# Mega8.net
KiCad netlist of a schematic drawn in EAGLE
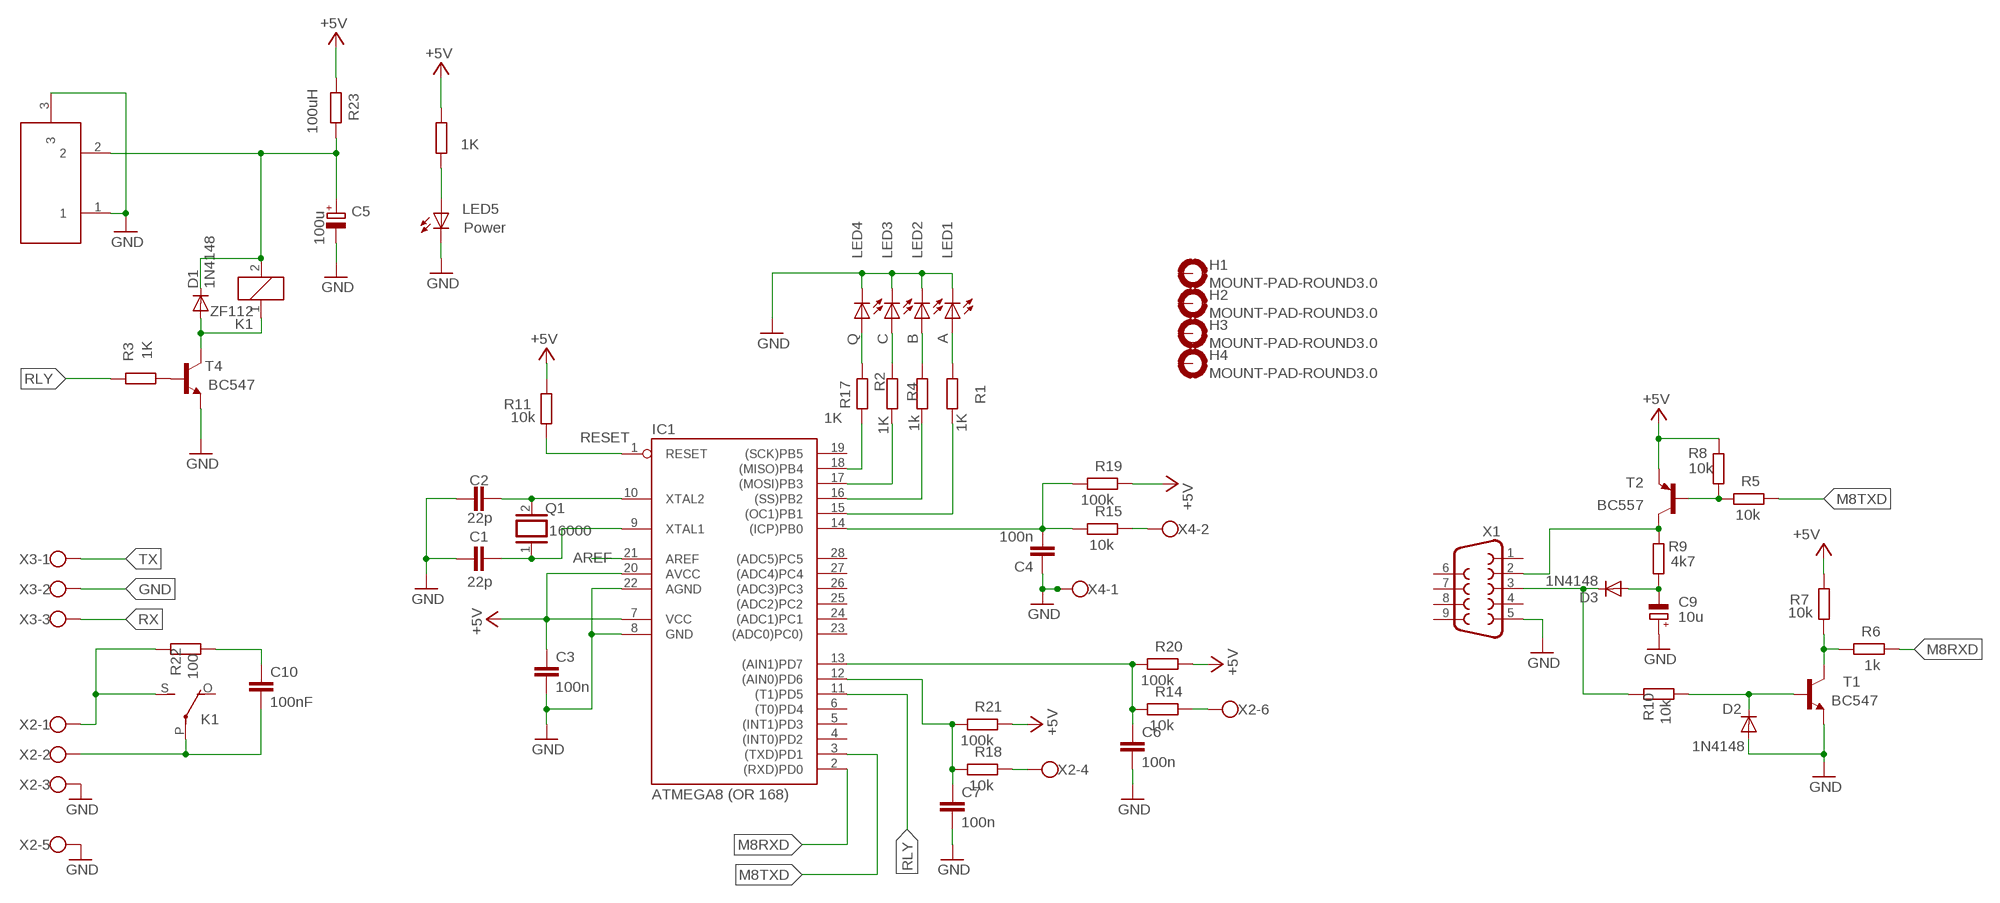
[diagram p0: schematic, sheet 1]

(export (version "E")
  (design (tool "Eeschema 10.0.6"))
  (components
    (comp (ref "C1")
      (value "22p")
      (footprint "eagle-import:C050-025X075")
      (libsource (lib "eagle-import") (part "C-EU050-025X075"))
    )
    (comp (ref "C2")
      (value "22p")
      (footprint "eagle-import:C050-025X075")
      (libsource (lib "eagle-import") (part "C-EU050-025X075"))
    )
    (comp (ref "C3")
      (value "100n")
      (footprint "eagle-import:C050-025X075")
      (libsource (lib "eagle-import") (part "C-EU050-025X075"))
    )
    (comp (ref "C4")
      (value "100n")
      (footprint "eagle-import:C050-025X075")
      (libsource (lib "eagle-import") (part "C-EU050-025X075"))
    )
    (comp (ref "C5")
      (value "100u")
      (footprint "eagle-import:E3,5-8")
      (libsource (lib "eagle-import") (part "CPOL-EUE3.5-8"))
    )
    (comp (ref "C6")
      (value "100n")
      (footprint "eagle-import:C050-025X075")
      (libsource (lib "eagle-import") (part "C-EU050-025X075"))
    )
    (comp (ref "C7")
      (value "100n")
      (footprint "eagle-import:C050-025X075")
      (libsource (lib "eagle-import") (part "C-EU050-025X075"))
    )
    (comp (ref "C9")
      (value "10u")
      (footprint "eagle-import:E5-6")
      (libsource (lib "eagle-import") (part "CPOL-EUE5-6"))
    )
    (comp (ref "C10")
      (value "100nF")
      (footprint "eagle-import:C102-043X133")
      (libsource (lib "eagle-import") (part "C-EU102-043X133"))
    )
    (comp (ref "D1")
      (value "1N4148")
      (footprint "eagle-import:DO35-10")
      (libsource (lib "eagle-import") (part "1N4148"))
    )
    (comp (ref "D2")
      (value "1N4148")
      (footprint "eagle-import:DO35-10")
      (libsource (lib "eagle-import") (part "1N4148"))
    )
    (comp (ref "D3")
      (value "1N4148")
      (footprint "eagle-import:DO35-10")
      (libsource (lib "eagle-import") (part "1N4148"))
    )
    (comp (ref "DC1")
      (value "DC21MMX")
      (footprint "eagle-import:DC-21MM")
      (libsource (lib "eagle-import") (part "DC21MMX"))
    )
    (comp (ref "H1")
      (value "MOUNT-PAD-ROUND3.0")
      (footprint "eagle-import:3,0-PAD")
      (libsource (lib "eagle-import") (part "MOUNT-PAD-ROUND3.0"))
    )
    (comp (ref "H2")
      (value "MOUNT-PAD-ROUND3.0")
      (footprint "eagle-import:3,0-PAD")
      (libsource (lib "eagle-import") (part "MOUNT-PAD-ROUND3.0"))
    )
    (comp (ref "H3")
      (value "MOUNT-PAD-ROUND3.0")
      (footprint "eagle-import:3,0-PAD")
      (libsource (lib "eagle-import") (part "MOUNT-PAD-ROUND3.0"))
    )
    (comp (ref "H4")
      (value "MOUNT-PAD-ROUND3.0")
      (footprint "eagle-import:3,0-PAD")
      (libsource (lib "eagle-import") (part "MOUNT-PAD-ROUND3.0"))
    )
    (comp (ref "IC1")
      (value "ATMEGA8 (OR 168)")
      (footprint "eagle-import:DIL28-3")
      (libsource (lib "eagle-import") (part "AT90S4433P"))
    )
    (comp (ref "K1")
      (value "ZF112")
      (footprint "eagle-import:ZF112")
      (libsource (lib "eagle-import") (part "ZF112"))
    )
    (comp (ref "LED1")
      (value "A")
      (footprint "eagle-import:LED3MM")
      (libsource (lib "eagle-import") (part "LED3MM"))
    )
    (comp (ref "LED2")
      (value "B")
      (footprint "eagle-import:LED3MM")
      (libsource (lib "eagle-import") (part "LED3MM"))
    )
    (comp (ref "LED3")
      (value "C")
      (footprint "eagle-import:LED3MM")
      (libsource (lib "eagle-import") (part "LED3MM"))
    )
    (comp (ref "LED4")
      (value "Q")
      (footprint "eagle-import:LED3MM")
      (libsource (lib "eagle-import") (part "LED3MM"))
    )
    (comp (ref "LED5")
      (value "Power")
      (footprint "eagle-import:LED3MM")
      (libsource (lib "eagle-import") (part "LED3MM"))
    )
    (comp (ref "Q1")
      (value "16000")
      (footprint "eagle-import:Q")
      (libsource (lib "eagle-import") (part "XTAL"))
    )
    (comp (ref "R1")
      (value "1K")
      (footprint "eagle-import:0207_10")
      (libsource (lib "eagle-import") (part "R-EU_0207/10"))
    )
    (comp (ref "R2")
      (value "1K")
      (footprint "eagle-import:0207_10")
      (libsource (lib "eagle-import") (part "R-EU_0207/10"))
    )
    (comp (ref "R3")
      (value "1K")
      (footprint "eagle-import:0207_10")
      (libsource (lib "eagle-import") (part "R-EU_0207/10"))
    )
    (comp (ref "R4")
      (value "1k")
      (footprint "eagle-import:0207_10")
      (libsource (lib "eagle-import") (part "R-EU_0207/10"))
    )
    (comp (ref "R5")
      (value "10k")
      (footprint "eagle-import:0207_10")
      (libsource (lib "eagle-import") (part "R-EU_0207/10"))
    )
    (comp (ref "R6")
      (value "1k")
      (footprint "eagle-import:0207_10")
      (libsource (lib "eagle-import") (part "R-EU_0207/10"))
    )
    (comp (ref "R7")
      (value "10k")
      (footprint "eagle-import:0207_10")
      (libsource (lib "eagle-import") (part "R-EU_0207/10"))
    )
    (comp (ref "R8")
      (value "10k")
      (footprint "eagle-import:0207_10")
      (libsource (lib "eagle-import") (part "R-EU_0207/10"))
    )
    (comp (ref "R9")
      (value "4k7")
      (footprint "eagle-import:0207_10")
      (libsource (lib "eagle-import") (part "R-EU_0207/10"))
    )
    (comp (ref "R10")
      (value "10k")
      (footprint "eagle-import:0207_10")
      (libsource (lib "eagle-import") (part "R-EU_0207/10"))
    )
    (comp (ref "R11")
      (value "10k")
      (footprint "eagle-import:0207_10")
      (libsource (lib "eagle-import") (part "R-EU_0207/10"))
    )
    (comp (ref "R14")
      (value "10k")
      (footprint "eagle-import:0207_10")
      (libsource (lib "eagle-import") (part "R-EU_0207/10"))
    )
    (comp (ref "R15")
      (value "10k")
      (footprint "eagle-import:0207_10")
      (libsource (lib "eagle-import") (part "R-EU_0207/10"))
    )
    (comp (ref "R16")
      (value "1K")
      (footprint "eagle-import:0207_10")
      (libsource (lib "eagle-import") (part "R-EU_0207/10"))
    )
    (comp (ref "R17")
      (value "1K")
      (footprint "eagle-import:0207_10")
      (libsource (lib "eagle-import") (part "R-EU_0207/10"))
    )
    (comp (ref "R18")
      (value "10k")
      (footprint "eagle-import:0207_10")
      (libsource (lib "eagle-import") (part "R-EU_0207/10"))
    )
    (comp (ref "R19")
      (value "100k")
      (footprint "eagle-import:0207_10")
      (libsource (lib "eagle-import") (part "R-EU_0207/10"))
    )
    (comp (ref "R20")
      (value "100k")
      (footprint "eagle-import:0207_10")
      (libsource (lib "eagle-import") (part "R-EU_0207/10"))
    )
    (comp (ref "R21")
      (value "100k")
      (footprint "eagle-import:0207_10")
      (libsource (lib "eagle-import") (part "R-EU_0207/10"))
    )
    (comp (ref "R22")
      (value "100")
      (footprint "eagle-import:0207_10")
      (libsource (lib "eagle-import") (part "R-EU_0207/10"))
    )
    (comp (ref "R23")
      (value "100uH")
      (footprint "eagle-import:0207_10")
      (libsource (lib "eagle-import") (part "R-EU_0207/10"))
    )
    (comp (ref "T1")
      (value "BC547")
      (footprint "eagle-import:TO92")
      (libsource (lib "eagle-import") (part "BC547"))
    )
    (comp (ref "T2")
      (value "BC557")
      (footprint "eagle-import:TO92-EBC")
      (libsource (lib "eagle-import") (part "-PNP-TO92-EBCBC557B"))
    )
    (comp (ref "T4")
      (value "BC547")
      (footprint "eagle-import:TO92")
      (libsource (lib "eagle-import") (part "BC547"))
    )
    (comp (ref "X1")
      (value "F09H")
      (footprint "eagle-import:F09H")
      (libsource (lib "eagle-import") (part "F09H"))
    )
    (comp (ref "X2")
      (value "W237-6")
      (footprint "eagle-import:W237-6")
      (libsource (lib "eagle-import") (part "W237-6"))
    )
    (comp (ref "X3")
      (value "W237-103")
      (footprint "eagle-import:W237-103")
      (fields (field (name "MPN") "237-103"))
      (libsource (lib "eagle-import") (part "W237-103"))
    )
    (comp (ref "X4")
      (value "W237-102")
      (footprint "eagle-import:W237-102")
      (fields (field (name "MPN") "237-102"))
      (libsource (lib "eagle-import") (part "W237-102"))
    )
  )
  (nets
    (net (code "1") (name "+5V") (class "Default")
      (node (ref "C3") (pin "1") (pinfunction "1_1") (pintype "passive"))
      (node (ref "IC1") (pin "20") (pinfunction "AVCC_20") (pintype "power_in"))
      (node (ref "IC1") (pin "7") (pinfunction "VCC_7") (pintype "power_in"))
      (node (ref "R11") (pin "2") (pinfunction "2_2") (pintype "passive"))
      (node (ref "R16") (pin "2") (pinfunction "2_2") (pintype "passive"))
      (node (ref "R19") (pin "1") (pinfunction "1_1") (pintype "passive"))
      (node (ref "R20") (pin "1") (pinfunction "1_1") (pintype "passive"))
      (node (ref "R21") (pin "1") (pinfunction "1_1") (pintype "passive"))
      (node (ref "R23") (pin "2") (pinfunction "2_2") (pintype "passive"))
      (node (ref "R7") (pin "2") (pinfunction "2_2") (pintype "passive"))
      (node (ref "R8") (pin "1") (pinfunction "1_1") (pintype "passive"))
      (node (ref "T2") (pin "E") (pinfunction "E_E") (pintype "passive"))
    )
    (net (code "2") (name "/AREF") (class "Default")
      (node (ref "IC1") (pin "21") (pinfunction "AREF_21") (pintype "power_in"))
    )
    (net (code "3") (name "/RESET") (class "Default")
      (node (ref "IC1") (pin "1") (pinfunction "RESET_1") (pintype "input"))
      (node (ref "R11") (pin "1") (pinfunction "1_1") (pintype "passive"))
    )
    (net (code "4") (name "GND") (class "Default")
      (node (ref "C1") (pin "1") (pinfunction "1_1") (pintype "passive"))
      (node (ref "C2") (pin "1") (pinfunction "1_1") (pintype "passive"))
      (node (ref "C3") (pin "2") (pinfunction "2_2") (pintype "passive"))
      (node (ref "C4") (pin "1") (pinfunction "1_1") (pintype "passive"))
      (node (ref "C5") (pin "-") (pinfunction "-_-") (pintype "passive"))
      (node (ref "C6") (pin "2") (pinfunction "2_2") (pintype "passive"))
      (node (ref "C7") (pin "2") (pinfunction "2_2") (pintype "passive"))
      (node (ref "C9") (pin "+") (pinfunction "+_+") (pintype "passive"))
      (node (ref "D2") (pin "A") (pinfunction "A_A") (pintype "passive"))
      (node (ref "DC1") (pin "1") (pinfunction "1_1") (pintype "power_in"))
      (node (ref "DC1") (pin "3") (pinfunction "3_3") (pintype "power_in"))
      (node (ref "IC1") (pin "22") (pinfunction "AGND_22") (pintype "power_in"))
      (node (ref "IC1") (pin "8") (pinfunction "GND_8") (pintype "power_in"))
      (node (ref "LED1") (pin "K") (pinfunction "C_K") (pintype "passive"))
      (node (ref "LED2") (pin "K") (pinfunction "C_K") (pintype "passive"))
      (node (ref "LED3") (pin "K") (pinfunction "C_K") (pintype "passive"))
      (node (ref "LED4") (pin "K") (pinfunction "C_K") (pintype "passive"))
      (node (ref "LED5") (pin "K") (pinfunction "C_K") (pintype "passive"))
      (node (ref "T1") (pin "1") (pinfunction "E_1") (pintype "passive"))
      (node (ref "T4") (pin "1") (pinfunction "E_1") (pintype "passive"))
      (node (ref "X1") (pin "5") (pinfunction "5_5") (pintype "passive"))
      (node (ref "X2") (pin "3") (pinfunction "KL_3") (pintype "passive"))
      (node (ref "X2") (pin "5") (pinfunction "KL_5") (pintype "passive"))
      (node (ref "X3") (pin "2") (pinfunction "KL_2") (pintype "passive"))
      (node (ref "X4") (pin "1") (pinfunction "KL_1") (pintype "passive"))
    )
    (net (code "5") (name "M8RXD") (class "Default")
      (node (ref "IC1") (pin "2") (pinfunction "(RXD)PD0_2") (pintype "bidirectional"))
      (node (ref "R6") (pin "1") (pinfunction "1_1") (pintype "passive"))
    )
    (net (code "6") (name "M8TXD") (class "Default")
      (node (ref "IC1") (pin "3") (pinfunction "(TXD)PD1_3") (pintype "bidirectional"))
      (node (ref "R5") (pin "1") (pinfunction "1_1") (pintype "passive"))
    )
    (net (code "7") (name "Net-(C5-Pad+)") (class "Default")
      (node (ref "C5") (pin "+") (pinfunction "+_+") (pintype "passive"))
      (node (ref "D1") (pin "C") (pinfunction "C_C") (pintype "passive"))
      (node (ref "DC1") (pin "2") (pinfunction "2_2") (pintype "power_in"))
      (node (ref "K1") (pin "2") (pinfunction "2_2") (pintype "passive"))
      (node (ref "R23") (pin "1") (pinfunction "1_1") (pintype "passive"))
    )
    (net (code "8") (name "Net-(C9-Pad-)") (class "Default")
      (node (ref "C9") (pin "-") (pinfunction "-_-") (pintype "passive"))
      (node (ref "D3") (pin "A") (pinfunction "A_A") (pintype "passive"))
      (node (ref "R9") (pin "1") (pinfunction "1_1") (pintype "passive"))
    )
    (net (code "9") (name "Net-(C10-Pad1)") (class "Default")
      (node (ref "C10") (pin "1") (pinfunction "1_1") (pintype "passive"))
      (node (ref "R22") (pin "1") (pinfunction "1_1") (pintype "passive"))
    )
    (net (code "10") (name "Net-(IC1-(AIN0)PD6)") (class "Default")
      (node (ref "C7") (pin "1") (pinfunction "1_1") (pintype "passive"))
      (node (ref "IC1") (pin "12") (pinfunction "(AIN0)PD6_12") (pintype "bidirectional"))
      (node (ref "R18") (pin "2") (pinfunction "2_2") (pintype "passive"))
      (node (ref "R21") (pin "2") (pinfunction "2_2") (pintype "passive"))
    )
    (net (code "11") (name "Net-(IC1-(AIN1)PD7)") (class "Default")
      (node (ref "C6") (pin "1") (pinfunction "1_1") (pintype "passive"))
      (node (ref "IC1") (pin "13") (pinfunction "(AIN1)PD7_13") (pintype "bidirectional"))
      (node (ref "R14") (pin "2") (pinfunction "2_2") (pintype "passive"))
      (node (ref "R20") (pin "2") (pinfunction "2_2") (pintype "passive"))
    )
    (net (code "12") (name "Net-(IC1-(ICP)PB0)") (class "Default")
      (node (ref "C4") (pin "2") (pinfunction "2_2") (pintype "passive"))
      (node (ref "IC1") (pin "14") (pinfunction "(ICP)PB0_14") (pintype "bidirectional"))
      (node (ref "R15") (pin "2") (pinfunction "2_2") (pintype "passive"))
      (node (ref "R19") (pin "2") (pinfunction "2_2") (pintype "passive"))
    )
    (net (code "13") (name "Net-(IC1-(MISO)PB4)") (class "Default")
      (node (ref "IC1") (pin "18") (pinfunction "(MISO)PB4_18") (pintype "bidirectional"))
      (node (ref "R17") (pin "2") (pinfunction "2_2") (pintype "passive"))
    )
    (net (code "14") (name "Net-(IC1-(MOSI)PB3)") (class "Default")
      (node (ref "IC1") (pin "17") (pinfunction "(MOSI)PB3_17") (pintype "bidirectional"))
      (node (ref "R2") (pin "2") (pinfunction "2_2") (pintype "passive"))
    )
    (net (code "15") (name "Net-(IC1-(OC1)PB1)") (class "Default")
      (node (ref "IC1") (pin "15") (pinfunction "(OC1)PB1_15") (pintype "bidirectional"))
      (node (ref "R1") (pin "2") (pinfunction "2_2") (pintype "passive"))
    )
    (net (code "16") (name "Net-(IC1-(SS)PB2)") (class "Default")
      (node (ref "IC1") (pin "16") (pinfunction "(SS)PB2_16") (pintype "bidirectional"))
      (node (ref "R4") (pin "2") (pinfunction "2_2") (pintype "passive"))
    )
    (net (code "17") (name "Net-(IC1-XTAL1)") (class "Default")
      (node (ref "C1") (pin "2") (pinfunction "2_2") (pintype "passive"))
      (node (ref "IC1") (pin "9") (pinfunction "XTAL1_9") (pintype "bidirectional"))
      (node (ref "Q1") (pin "1") (pinfunction "1_1") (pintype "passive"))
    )
    (net (code "18") (name "Net-(IC1-XTAL2)") (class "Default")
      (node (ref "C2") (pin "2") (pinfunction "2_2") (pintype "passive"))
      (node (ref "IC1") (pin "10") (pinfunction "XTAL2_10") (pintype "bidirectional"))
      (node (ref "Q1") (pin "2") (pinfunction "2_2") (pintype "passive"))
    )
    (net (code "19") (name "Net-(LED1-PadA)") (class "Default")
      (node (ref "LED1") (pin "A") (pinfunction "A_A") (pintype "passive"))
      (node (ref "R1") (pin "1") (pinfunction "1_1") (pintype "passive"))
    )
    (net (code "20") (name "Net-(LED2-PadA)") (class "Default")
      (node (ref "LED2") (pin "A") (pinfunction "A_A") (pintype "passive"))
      (node (ref "R4") (pin "1") (pinfunction "1_1") (pintype "passive"))
    )
    (net (code "21") (name "Net-(LED3-PadA)") (class "Default")
      (node (ref "LED3") (pin "A") (pinfunction "A_A") (pintype "passive"))
      (node (ref "R2") (pin "1") (pinfunction "1_1") (pintype "passive"))
    )
    (net (code "22") (name "Net-(LED4-PadA)") (class "Default")
      (node (ref "LED4") (pin "A") (pinfunction "A_A") (pintype "passive"))
      (node (ref "R17") (pin "1") (pinfunction "1_1") (pintype "passive"))
    )
    (net (code "23") (name "Net-(LED5-PadA)") (class "Default")
      (node (ref "LED5") (pin "A") (pinfunction "A_A") (pintype "passive"))
      (node (ref "R16") (pin "1") (pinfunction "1_1") (pintype "passive"))
    )
    (net (code "24") (name "Net-(R5-Pad2)") (class "Default")
      (node (ref "R5") (pin "2") (pinfunction "2_2") (pintype "passive"))
      (node (ref "R8") (pin "2") (pinfunction "2_2") (pintype "passive"))
      (node (ref "T2") (pin "B") (pinfunction "B_B") (pintype "passive"))
    )
    (net (code "25") (name "Net-(T1-B)") (class "Default")
      (node (ref "D2") (pin "C") (pinfunction "C_C") (pintype "passive"))
      (node (ref "R10") (pin "1") (pinfunction "1_1") (pintype "passive"))
      (node (ref "T1") (pin "2") (pinfunction "B_2") (pintype "passive"))
    )
    (net (code "26") (name "Net-(T1-C)") (class "Default")
      (node (ref "R6") (pin "2") (pinfunction "2_2") (pintype "passive"))
      (node (ref "R7") (pin "1") (pinfunction "1_1") (pintype "passive"))
      (node (ref "T1") (pin "3") (pinfunction "C_3") (pintype "passive"))
    )
    (net (code "27") (name "Net-(T4-B)") (class "Default")
      (node (ref "R3") (pin "1") (pinfunction "1_1") (pintype "passive"))
      (node (ref "T4") (pin "2") (pinfunction "B_2") (pintype "passive"))
    )
    (net (code "28") (name "Net-(T4-C)") (class "Default")
      (node (ref "D1") (pin "A") (pinfunction "A_A") (pintype "passive"))
      (node (ref "K1") (pin "1") (pinfunction "1_1") (pintype "passive"))
      (node (ref "T4") (pin "3") (pinfunction "C_3") (pintype "passive"))
    )
    (net (code "29") (name "Net-(X2A-KL)") (class "Default")
      (node (ref "K1") (pin "S") (pinfunction "S_S") (pintype "passive"))
      (node (ref "R22") (pin "2") (pinfunction "2_2") (pintype "passive"))
      (node (ref "X2") (pin "1") (pinfunction "KL_1") (pintype "passive"))
    )
    (net (code "30") (name "Net-(X2B-KL)") (class "Default")
      (node (ref "C10") (pin "2") (pinfunction "2_2") (pintype "passive"))
      (node (ref "K1") (pin "P") (pinfunction "P_P") (pintype "passive"))
      (node (ref "X2") (pin "2") (pinfunction "KL_2") (pintype "passive"))
    )
    (net (code "31") (name "Net-(X2D-KL)") (class "Default")
      (node (ref "R18") (pin "1") (pinfunction "1_1") (pintype "passive"))
      (node (ref "X2") (pin "4") (pinfunction "KL_4") (pintype "passive"))
    )
    (net (code "32") (name "Net-(X2F-KL)") (class "Default")
      (node (ref "R14") (pin "1") (pinfunction "1_1") (pintype "passive"))
      (node (ref "X2") (pin "6") (pinfunction "KL_6") (pintype "passive"))
    )
    (net (code "33") (name "Net-(X4B-KL)") (class "Default")
      (node (ref "R15") (pin "1") (pinfunction "1_1") (pintype "passive"))
      (node (ref "X4") (pin "2") (pinfunction "KL_2") (pintype "passive"))
    )
    (net (code "34") (name "RLY") (class "Default")
      (node (ref "IC1") (pin "11") (pinfunction "(T1)PD5_11") (pintype "bidirectional"))
      (node (ref "R3") (pin "2") (pinfunction "2_2") (pintype "passive"))
    )
    (net (code "35") (name "RX") (class "Default")
      (node (ref "D3") (pin "C") (pinfunction "C_C") (pintype "passive"))
      (node (ref "R10") (pin "2") (pinfunction "2_2") (pintype "passive"))
      (node (ref "X1") (pin "3") (pinfunction "3_3") (pintype "passive"))
      (node (ref "X3") (pin "3") (pinfunction "KL_3") (pintype "passive"))
    )
    (net (code "36") (name "TX") (class "Default")
      (node (ref "R9") (pin "2") (pinfunction "2_2") (pintype "passive"))
      (node (ref "T2") (pin "C") (pinfunction "C_C") (pintype "passive"))
      (node (ref "X1") (pin "2") (pinfunction "2_2") (pintype "passive"))
      (node (ref "X3") (pin "1") (pinfunction "KL_1") (pintype "passive"))
    )
    (net (code "37") (name "unconnected-(H1-MOUNT-PadB3,0)") (class "Default")
      (node (ref "H1") (pin "B3,0") (pinfunction "MOUNT_B3,0") (pintype "passive"))
    )
    (net (code "38") (name "unconnected-(H2-MOUNT-PadB3,0)") (class "Default")
      (node (ref "H2") (pin "B3,0") (pinfunction "MOUNT_B3,0") (pintype "passive"))
    )
    (net (code "39") (name "unconnected-(H3-MOUNT-PadB3,0)") (class "Default")
      (node (ref "H3") (pin "B3,0") (pinfunction "MOUNT_B3,0") (pintype "passive"))
    )
    (net (code "40") (name "unconnected-(H4-MOUNT-PadB3,0)") (class "Default")
      (node (ref "H4") (pin "B3,0") (pinfunction "MOUNT_B3,0") (pintype "passive"))
    )
    (net (code "41") (name "unconnected-(IC1-(ADC0)PC0)-Pad23)") (class "Default")
      (node (ref "IC1") (pin "23") (pinfunction "(ADC0)PC0)_23") (pintype "bidirectional"))
    )
    (net (code "42") (name "unconnected-(IC1-(ADC1)PC1-Pad24)") (class "Default")
      (node (ref "IC1") (pin "24") (pinfunction "(ADC1)PC1_24") (pintype "bidirectional"))
    )
    (net (code "43") (name "unconnected-(IC1-(ADC2)PC2-Pad25)") (class "Default")
      (node (ref "IC1") (pin "25") (pinfunction "(ADC2)PC2_25") (pintype "bidirectional"))
    )
    (net (code "44") (name "unconnected-(IC1-(ADC3)PC3-Pad26)") (class "Default")
      (node (ref "IC1") (pin "26") (pinfunction "(ADC3)PC3_26") (pintype "bidirectional"))
    )
    (net (code "45") (name "unconnected-(IC1-(ADC4)PC4-Pad27)") (class "Default")
      (node (ref "IC1") (pin "27") (pinfunction "(ADC4)PC4_27") (pintype "bidirectional"))
    )
    (net (code "46") (name "unconnected-(IC1-(ADC5)PC5-Pad28)") (class "Default")
      (node (ref "IC1") (pin "28") (pinfunction "(ADC5)PC5_28") (pintype "bidirectional"))
    )
    (net (code "47") (name "unconnected-(IC1-(INT0)PD2-Pad4)") (class "Default")
      (node (ref "IC1") (pin "4") (pinfunction "(INT0)PD2_4") (pintype "bidirectional"))
    )
    (net (code "48") (name "unconnected-(IC1-(INT1)PD3-Pad5)") (class "Default")
      (node (ref "IC1") (pin "5") (pinfunction "(INT1)PD3_5") (pintype "bidirectional"))
    )
    (net (code "49") (name "unconnected-(IC1-(SCK)PB5-Pad19)") (class "Default")
      (node (ref "IC1") (pin "19") (pinfunction "(SCK)PB5_19") (pintype "bidirectional"))
    )
    (net (code "50") (name "unconnected-(IC1-(T0)PD4-Pad6)") (class "Default")
      (node (ref "IC1") (pin "6") (pinfunction "(T0)PD4_6") (pintype "bidirectional"))
    )
    (net (code "51") (name "unconnected-(K1-PadO)") (class "Default")
      (node (ref "K1") (pin "O") (pinfunction "O_O") (pintype "passive"))
    )
    (net (code "52") (name "unconnected-(X1-Pad1)") (class "Default")
      (node (ref "X1") (pin "1") (pinfunction "1_1") (pintype "passive"))
    )
    (net (code "53") (name "unconnected-(X1-Pad4)") (class "Default")
      (node (ref "X1") (pin "4") (pinfunction "4_4") (pintype "passive"))
    )
    (net (code "54") (name "unconnected-(X1-Pad6)") (class "Default")
      (node (ref "X1") (pin "6") (pinfunction "6_6") (pintype "passive"))
    )
    (net (code "55") (name "unconnected-(X1-Pad7)") (class "Default")
      (node (ref "X1") (pin "7") (pinfunction "7_7") (pintype "passive"))
    )
    (net (code "56") (name "unconnected-(X1-Pad8)") (class "Default")
      (node (ref "X1") (pin "8") (pinfunction "8_8") (pintype "passive"))
    )
    (net (code "57") (name "unconnected-(X1-Pad9)") (class "Default")
      (node (ref "X1") (pin "9") (pinfunction "9_9") (pintype "passive"))
    )
  )
)
